# Power.net
KiCad netlist of a schematic drawn in Altium Designer
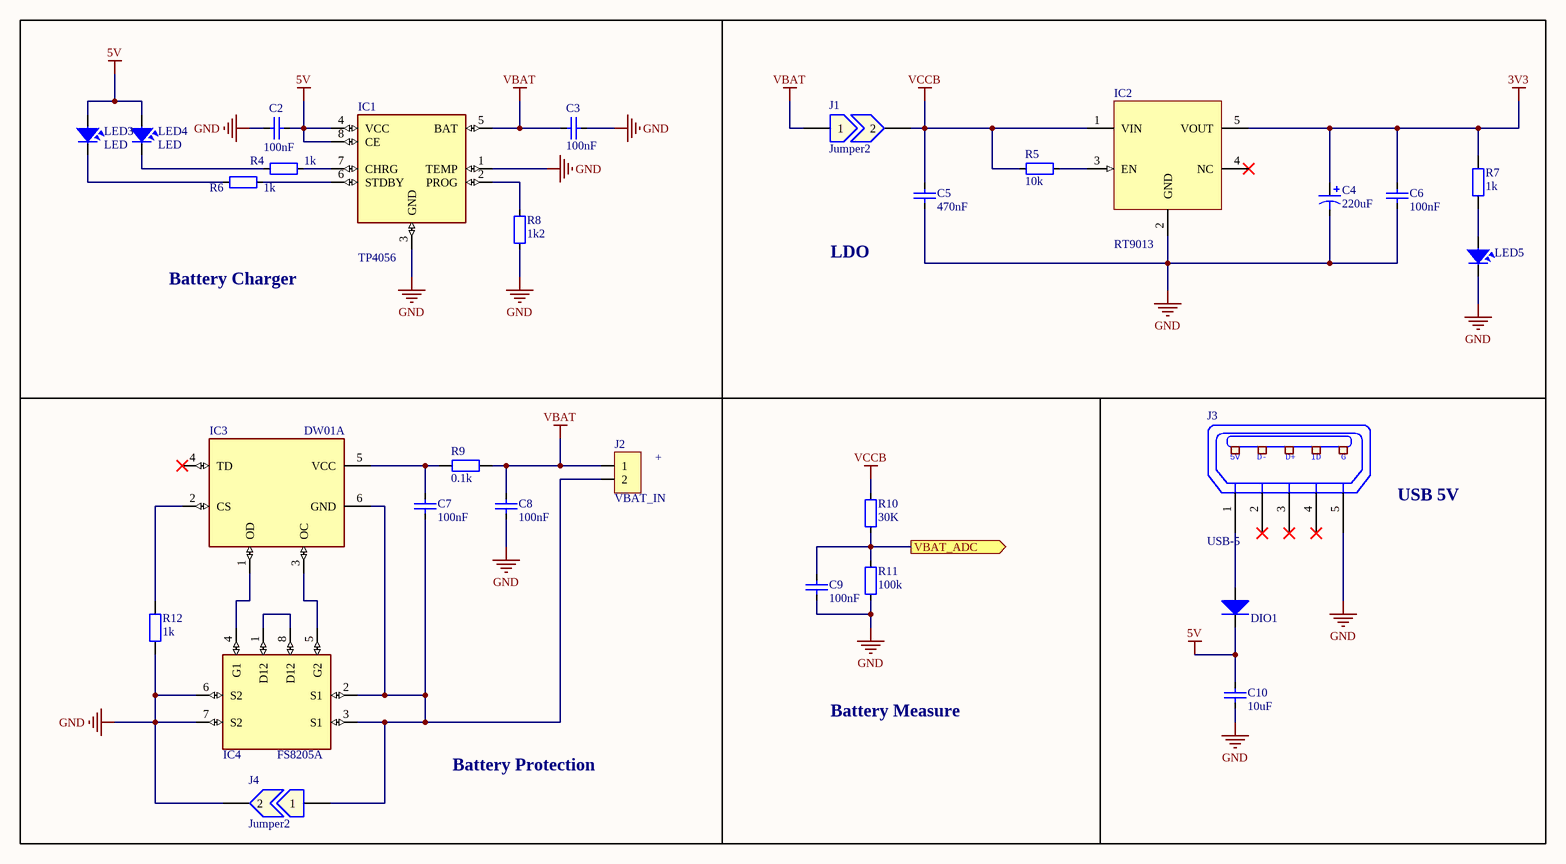
[diagram p0: Power.SchDoc]

(export (version "E")
  (design (tool "Eeschema 10.0.6"))
  (components
    (comp (ref "C2")
      (value "100nF")
      (footprint "CAP_0805")
      (description "Capacitor")
      (fields (field (name "PUBLISHER") "Altium Limited"))
      (libsource (lib "My Library") (part "CapSMD"))
    )
    (comp (ref "C3")
      (value "100nF")
      (footprint "CAP_0805")
      (description "Capacitor")
      (fields (field (name "PUBLISHER") "Altium Limited"))
      (libsource (lib "My Library") (part "CapSMD"))
    )
    (comp (ref "C4")
      (value "220uF")
      (footprint "CAP_TANTALUM_3216")
      (description "Polarized Capacitor (Axial)")
      (fields (field (name "PUBLISHER") "Altium Limited"))
      (libsource (lib "My Library") (part "Cap Pol"))
    )
    (comp (ref "C5")
      (value "470nF")
      (footprint "CAP_0805")
      (description "Capacitor")
      (fields (field (name "PUBLISHER") "Altium Limited"))
      (libsource (lib "My Library") (part "CapSMD"))
    )
    (comp (ref "C6")
      (value "100nF")
      (footprint "CAP_0805")
      (description "Capacitor")
      (fields (field (name "PUBLISHER") "Altium Limited"))
      (libsource (lib "My Library") (part "CapSMD"))
    )
    (comp (ref "C7")
      (value "100nF")
      (footprint "CAP_0805")
      (description "Capacitor")
      (fields (field (name "PUBLISHER") "Altium Limited"))
      (libsource (lib "My Library") (part "CapSMD"))
    )
    (comp (ref "C8")
      (value "100nF")
      (footprint "CAP_0805")
      (description "Capacitor")
      (fields (field (name "PUBLISHER") "Altium Limited"))
      (libsource (lib "My Library") (part "CapSMD"))
    )
    (comp (ref "C9")
      (value "100nF")
      (footprint "CAP_0805")
      (description "Capacitor")
      (fields (field (name "PUBLISHER") "Altium Limited"))
      (libsource (lib "My Library") (part "CapSMD"))
    )
    (comp (ref "C10")
      (value "10uF")
      (footprint "CAP_0805")
      (description "Capacitor")
      (fields (field (name "PUBLISHER") "Altium Limited"))
      (libsource (lib "My Library") (part "CapSMD"))
    )
    (comp (ref "DIO1")
      (value "Diode SMD")
      (footprint "DIO-214AC(SMA)")
      (description "Default Diode")
      (fields (field (name "PUBLISHER") "Altium Limited"))
      (libsource (lib "My Library") (part "Diode SMD"))
    )
    (comp (ref "IC1")
      (value "TP4056")
      (footprint "TP4056")
      (description "Complete single cell Li-Ion battery with a constant current / constant voltage linear charger")
      (libsource (lib "My Library") (part "TP4056"))
    )
    (comp (ref "IC2")
      (value "RT9013")
      (footprint "SOT23-5")
      (description "https://linhkien.cxt.vn/5435-rt9013-33gb-ic-reg-linear-33v-500ma-sot23-5.html")
      (libsource (lib "My Library") (part "RT9013"))
    )
    (comp (ref "IC3")
      (value "DW01A")
      (footprint "SOT23-6")
      (description "One Cell Lithium-ion/Polymer Battery Protection IC")
      (libsource (lib "My Library") (part "DW01A"))
    )
    (comp (ref "IC4") (value "FS8205A") (footprint "FS8205A") (libsource (lib "My Library") (part "FS8205A")))
    (comp (ref "J1")
      (value "Jumper2")
      (footprint "JUMPER2")
      (description "Jumper, 2-Pin")
      (libsource (lib "Main") (part "Jumper2"))
    )
    (comp (ref "J2")
      (value "VBAT_IN")
      (footprint "JP2-D1T")
      (description "WR-PHD 2.54 mm Angled Socket Header")
      (fields
        (field (name "MANUFACTURER") "Würth Elektronik eiSos GmbH")
        (field (name "PARTNO") "613002143121")
        (field (name "CREATED BY") "Karrer Zheng")
      )
      (libsource (lib "My Library") (part "JP2"))
    )
    (comp (ref "J3")
      (value "USB-5")
      (footprint "USB-M1")
      (fields
        (field (name "MANUFACTURER") "FCI")
        (field (name "MANUFACTURER PART NUMBER") "10118193-0001LF")
        (field (name ".CREATOR") "MM")
        (field (name ".CHECKED PCB") "RF")
        (field (name ".CHECKED SCH") "MM")
      )
      (libsource (lib "My Library") (part "USB-5"))
    )
    (comp (ref "J4")
      (value "Jumper2")
      (footprint "JUMPER2")
      (description "Jumper, 2-Pin")
      (libsource (lib "My Library") (part "Jumper2"))
    )
    (comp (ref "LED3")
      (value "LED")
      (footprint "LED-0805-Red")
      (description "LED Single colour Green and Red")
      (libsource (lib "My Library") (part "LED"))
    )
    (comp (ref "LED4")
      (value "LED")
      (footprint "LED-0805-Green")
      (description "LED Single colour Green and Red")
      (libsource (lib "My Library") (part "LED"))
    )
    (comp (ref "LED5")
      (value "~")
      (footprint "LED-0805-Red")
      (description "LED Single colour Green and Red")
      (libsource (lib "Main") (part "LED"))
    )
    (comp (ref "R4")
      (value "1k")
      (footprint "RES-SMD-0805")
      (description "Resistor")
      (fields
        (field (name "MANUFACTURER") "Generic Components")
        (field (name "PUBLISHER") "Altium Hobart Technology Centre")
      )
      (libsource (lib "My Library") (part "Resistor - SMD"))
    )
    (comp (ref "R5")
      (value "10k")
      (footprint "RES-SMD-0805")
      (description "Resistor")
      (fields
        (field (name "MANUFACTURER") "Generic Components")
        (field (name "PUBLISHER") "Altium Hobart Technology Centre")
      )
      (libsource (lib "My Library") (part "Resistor - SMD"))
    )
    (comp (ref "R6")
      (value "1k")
      (footprint "RES-SMD-0805")
      (description "Resistor")
      (fields
        (field (name "MANUFACTURER") "Generic Components")
        (field (name "PUBLISHER") "Altium Hobart Technology Centre")
      )
      (libsource (lib "My Library") (part "Resistor - SMD"))
    )
    (comp (ref "R7")
      (value "1k")
      (footprint "RES-SMD-0805")
      (description "Resistor SMD")
      (fields
        (field (name "MANUFACTURER") "Generic Components")
        (field (name "PUBLISHER") "Altium Hobart Technology Centre")
      )
      (libsource (lib "Main") (part "Resistor - SMD"))
    )
    (comp (ref "R8")
      (value "1k2")
      (footprint "RES-SMD-0805")
      (description "Resistor")
      (fields
        (field (name "MANUFACTURER") "Generic Components")
        (field (name "PUBLISHER") "Altium Hobart Technology Centre")
      )
      (libsource (lib "My Library") (part "Resistor - SMD"))
    )
    (comp (ref "R9")
      (value "0.1k")
      (footprint "RES-SMD-0805")
      (description "Resistor SMD")
      (fields
        (field (name "MANUFACTURER") "Generic Components")
        (field (name "PUBLISHER") "Altium Hobart Technology Centre")
      )
      (libsource (lib "") (part "Resistor - SMD_1"))
    )
    (comp (ref "R10")
      (value "30K")
      (footprint "RES-SMD-0805")
      (description "Resistor")
      (fields
        (field (name "MANUFACTURER") "Generic Components")
        (field (name "PUBLISHER") "Altium Hobart Technology Centre")
      )
      (libsource (lib "My Library") (part "Resistor - SMD"))
    )
    (comp (ref "R11")
      (value "100k")
      (footprint "RES-SMD-0805")
      (description "Resistor")
      (fields
        (field (name "MANUFACTURER") "Generic Components")
        (field (name "PUBLISHER") "Altium Hobart Technology Centre")
      )
      (libsource (lib "My Library") (part "Resistor - SMD"))
    )
    (comp (ref "R12")
      (value "1k")
      (footprint "RES-SMD-0805")
      (description "Resistor SMD")
      (fields
        (field (name "MANUFACTURER") "Generic Components")
        (field (name "PUBLISHER") "Altium Hobart Technology Centre")
      )
      (libsource (lib "") (part "Resistor - SMD_1"))
    )
  )
  (nets
    (net (code "1") (name "/VBAT_ADC") (class "Default")
      (node (ref "C9") (pin "2") (pinfunction "2_2") (pintype "passive"))
      (node (ref "R10") (pin "2") (pinfunction "2_2") (pintype "passive"))
      (node (ref "R11") (pin "1") (pinfunction "1_1") (pintype "passive"))
    )
    (net (code "2") (name "3V3") (class "Default")
      (node (ref "C4") (pin "1") (pinfunction "1_1") (pintype "passive"))
      (node (ref "C6") (pin "1") (pinfunction "1_1") (pintype "passive"))
      (node (ref "IC2") (pin "5") (pinfunction "VOUT_5") (pintype "power_in"))
      (node (ref "R7") (pin "2") (pinfunction "2_2") (pintype "passive"))
    )
    (net (code "3") (name "5V") (class "Default")
      (node (ref "C10") (pin "2") (pinfunction "2_2") (pintype "passive"))
      (node (ref "C2") (pin "1") (pinfunction "1_1") (pintype "passive"))
      (node (ref "DIO1") (pin "2") (pinfunction "K_2") (pintype "passive"))
      (node (ref "IC1") (pin "4") (pinfunction "VCC_4") (pintype "bidirectional"))
      (node (ref "IC1") (pin "8") (pinfunction "CE_8") (pintype "bidirectional"))
      (node (ref "LED3") (pin "1") (pinfunction "1_1") (pintype "passive"))
      (node (ref "LED4") (pin "1") (pinfunction "1_1") (pintype "passive"))
    )
    (net (code "4") (name "GND") (class "Default")
      (node (ref "C10") (pin "1") (pinfunction "1_1") (pintype "passive"))
      (node (ref "C2") (pin "2") (pinfunction "2_2") (pintype "passive"))
      (node (ref "C3") (pin "1") (pinfunction "1_1") (pintype "passive"))
      (node (ref "C4") (pin "2") (pinfunction "2_2") (pintype "passive"))
      (node (ref "C5") (pin "2") (pinfunction "2_2") (pintype "passive"))
      (node (ref "C6") (pin "2") (pinfunction "2_2") (pintype "passive"))
      (node (ref "C8") (pin "1") (pinfunction "1_1") (pintype "passive"))
      (node (ref "C9") (pin "1") (pinfunction "1_1") (pintype "passive"))
      (node (ref "IC1") (pin "1") (pinfunction "TEMP_1") (pintype "bidirectional"))
      (node (ref "IC1") (pin "3") (pinfunction "GND_3") (pintype "bidirectional"))
      (node (ref "IC2") (pin "2") (pinfunction "GND_2") (pintype "power_in"))
      (node (ref "IC4") (pin "6") (pinfunction "S2_6") (pintype "bidirectional"))
      (node (ref "IC4") (pin "7") (pinfunction "S2_7") (pintype "bidirectional"))
      (node (ref "J3") (pin "5") (pinfunction "P5_5") (pintype "passive"))
      (node (ref "J4") (pin "2") (pinfunction "2_2") (pintype "passive"))
      (node (ref "LED5") (pin "2") (pinfunction "2_2") (pintype "passive"))
      (node (ref "R11") (pin "2") (pinfunction "2_2") (pintype "passive"))
      (node (ref "R12") (pin "2") (pinfunction "2_2") (pintype "passive"))
      (node (ref "R8") (pin "1") (pinfunction "1_1") (pintype "passive"))
    )
    (net (code "5") (name "Net-(DIO1-A)") (class "Default")
      (node (ref "DIO1") (pin "1") (pinfunction "A_1") (pintype "passive"))
      (node (ref "J3") (pin "1") (pinfunction "P1_1") (pintype "passive"))
    )
    (net (code "6") (name "Net-(IC1-CHRG)") (class "Default")
      (node (ref "IC1") (pin "7") (pinfunction "CHRG_7") (pintype "bidirectional"))
      (node (ref "R4") (pin "1") (pinfunction "1_1") (pintype "passive"))
    )
    (net (code "7") (name "Net-(IC1-PROG)") (class "Default")
      (node (ref "IC1") (pin "2") (pinfunction "PROG_2") (pintype "bidirectional"))
      (node (ref "R8") (pin "2") (pinfunction "2_2") (pintype "passive"))
    )
    (net (code "8") (name "Net-(IC1-STDBY)") (class "Default")
      (node (ref "IC1") (pin "6") (pinfunction "STDBY_6") (pintype "bidirectional"))
      (node (ref "R6") (pin "1") (pinfunction "1_1") (pintype "passive"))
    )
    (net (code "9") (name "Net-(IC2-EN)") (class "Default")
      (node (ref "IC2") (pin "3") (pinfunction "EN_3") (pintype "input"))
      (node (ref "R5") (pin "1") (pinfunction "1_1") (pintype "passive"))
    )
    (net (code "10") (name "Net-(IC3-CS)") (class "Default")
      (node (ref "IC3") (pin "2") (pinfunction "CS_2") (pintype "bidirectional"))
      (node (ref "R12") (pin "1") (pinfunction "1_1") (pintype "passive"))
    )
    (net (code "11") (name "Net-(IC3-GND)") (class "Default")
      (node (ref "C7") (pin "1") (pinfunction "1_1") (pintype "passive"))
      (node (ref "IC3") (pin "6") (pinfunction "GND_6") (pintype "power_in"))
      (node (ref "IC4") (pin "2") (pinfunction "S1_2") (pintype "bidirectional"))
      (node (ref "IC4") (pin "3") (pinfunction "S1_3") (pintype "bidirectional"))
      (node (ref "J2") (pin "2") (pinfunction "2_2") (pintype "passive"))
      (node (ref "J4") (pin "1") (pinfunction "1_1") (pintype "passive"))
    )
    (net (code "12") (name "Net-(IC3-OC)") (class "Default")
      (node (ref "IC3") (pin "3") (pinfunction "OC_3") (pintype "bidirectional"))
      (node (ref "IC4") (pin "5") (pinfunction "G2_5") (pintype "bidirectional"))
    )
    (net (code "13") (name "Net-(IC3-OD)") (class "Default")
      (node (ref "IC3") (pin "1") (pinfunction "OD_1") (pintype "bidirectional"))
      (node (ref "IC4") (pin "4") (pinfunction "G1_4") (pintype "bidirectional"))
    )
    (net (code "14") (name "Net-(IC3-VCC)") (class "Default")
      (node (ref "C7") (pin "2") (pinfunction "2_2") (pintype "passive"))
      (node (ref "IC3") (pin "5") (pinfunction "VCC_5") (pintype "power_in"))
      (node (ref "R9") (pin "1") (pinfunction "1_1") (pintype "passive"))
    )
    (net (code "15") (name "Net-(IC4-D12-Pad1)") (class "Default")
      (node (ref "IC4") (pin "1") (pinfunction "D12_1") (pintype "bidirectional"))
      (node (ref "IC4") (pin "8") (pinfunction "D12_8") (pintype "bidirectional"))
    )
    (net (code "16") (name "Net-(LED3-Pad2)") (class "Default")
      (node (ref "LED3") (pin "2") (pinfunction "2_2") (pintype "passive"))
      (node (ref "R6") (pin "2") (pinfunction "2_2") (pintype "passive"))
    )
    (net (code "17") (name "Net-(LED4-Pad2)") (class "Default")
      (node (ref "LED4") (pin "2") (pinfunction "2_2") (pintype "passive"))
      (node (ref "R4") (pin "2") (pinfunction "2_2") (pintype "passive"))
    )
    (net (code "18") (name "Net-(LED5-Pad1)") (class "Default")
      (node (ref "LED5") (pin "1") (pinfunction "1_1") (pintype "passive"))
      (node (ref "R7") (pin "1") (pinfunction "1_1") (pintype "passive"))
    )
    (net (code "19") (name "VBAT") (class "Default")
      (node (ref "C3") (pin "2") (pinfunction "2_2") (pintype "passive"))
      (node (ref "C8") (pin "2") (pinfunction "2_2") (pintype "passive"))
      (node (ref "IC1") (pin "5") (pinfunction "BAT_5") (pintype "bidirectional"))
      (node (ref "J1") (pin "1") (pinfunction "1_1") (pintype "passive"))
      (node (ref "J2") (pin "1") (pinfunction "1_1") (pintype "passive"))
      (node (ref "R9") (pin "2") (pinfunction "2_2") (pintype "passive"))
    )
    (net (code "20") (name "VCCB") (class "Default")
      (node (ref "C5") (pin "1") (pinfunction "1_1") (pintype "passive"))
      (node (ref "IC2") (pin "1") (pinfunction "VIN_1") (pintype "power_in"))
      (node (ref "J1") (pin "2") (pinfunction "2_2") (pintype "passive"))
      (node (ref "R10") (pin "1") (pinfunction "1_1") (pintype "passive"))
      (node (ref "R5") (pin "2") (pinfunction "2_2") (pintype "passive"))
    )
    (net (code "21") (name "unconnected-(IC2-NC-Pad4)") (class "Default")
      (node (ref "IC2") (pin "4") (pinfunction "NC_4") (pintype "passive+no_connect"))
    )
    (net (code "22") (name "unconnected-(IC3-TD-Pad4)") (class "Default")
      (node (ref "IC3") (pin "4") (pinfunction "TD_4") (pintype "bidirectional+no_connect"))
    )
    (net (code "23") (name "unconnected-(J3-P2-Pad2)") (class "Default")
      (node (ref "J3") (pin "2") (pinfunction "P2_2") (pintype "passive+no_connect"))
    )
    (net (code "24") (name "unconnected-(J3-P3-Pad3)") (class "Default")
      (node (ref "J3") (pin "3") (pinfunction "P3_3") (pintype "passive+no_connect"))
    )
    (net (code "25") (name "unconnected-(J3-P4-Pad4)") (class "Default")
      (node (ref "J3") (pin "4") (pinfunction "P4_4") (pintype "passive+no_connect"))
    )
  )
)
